# 1_interface.net
KiCad netlist of a schematic drawn in Altium Designer
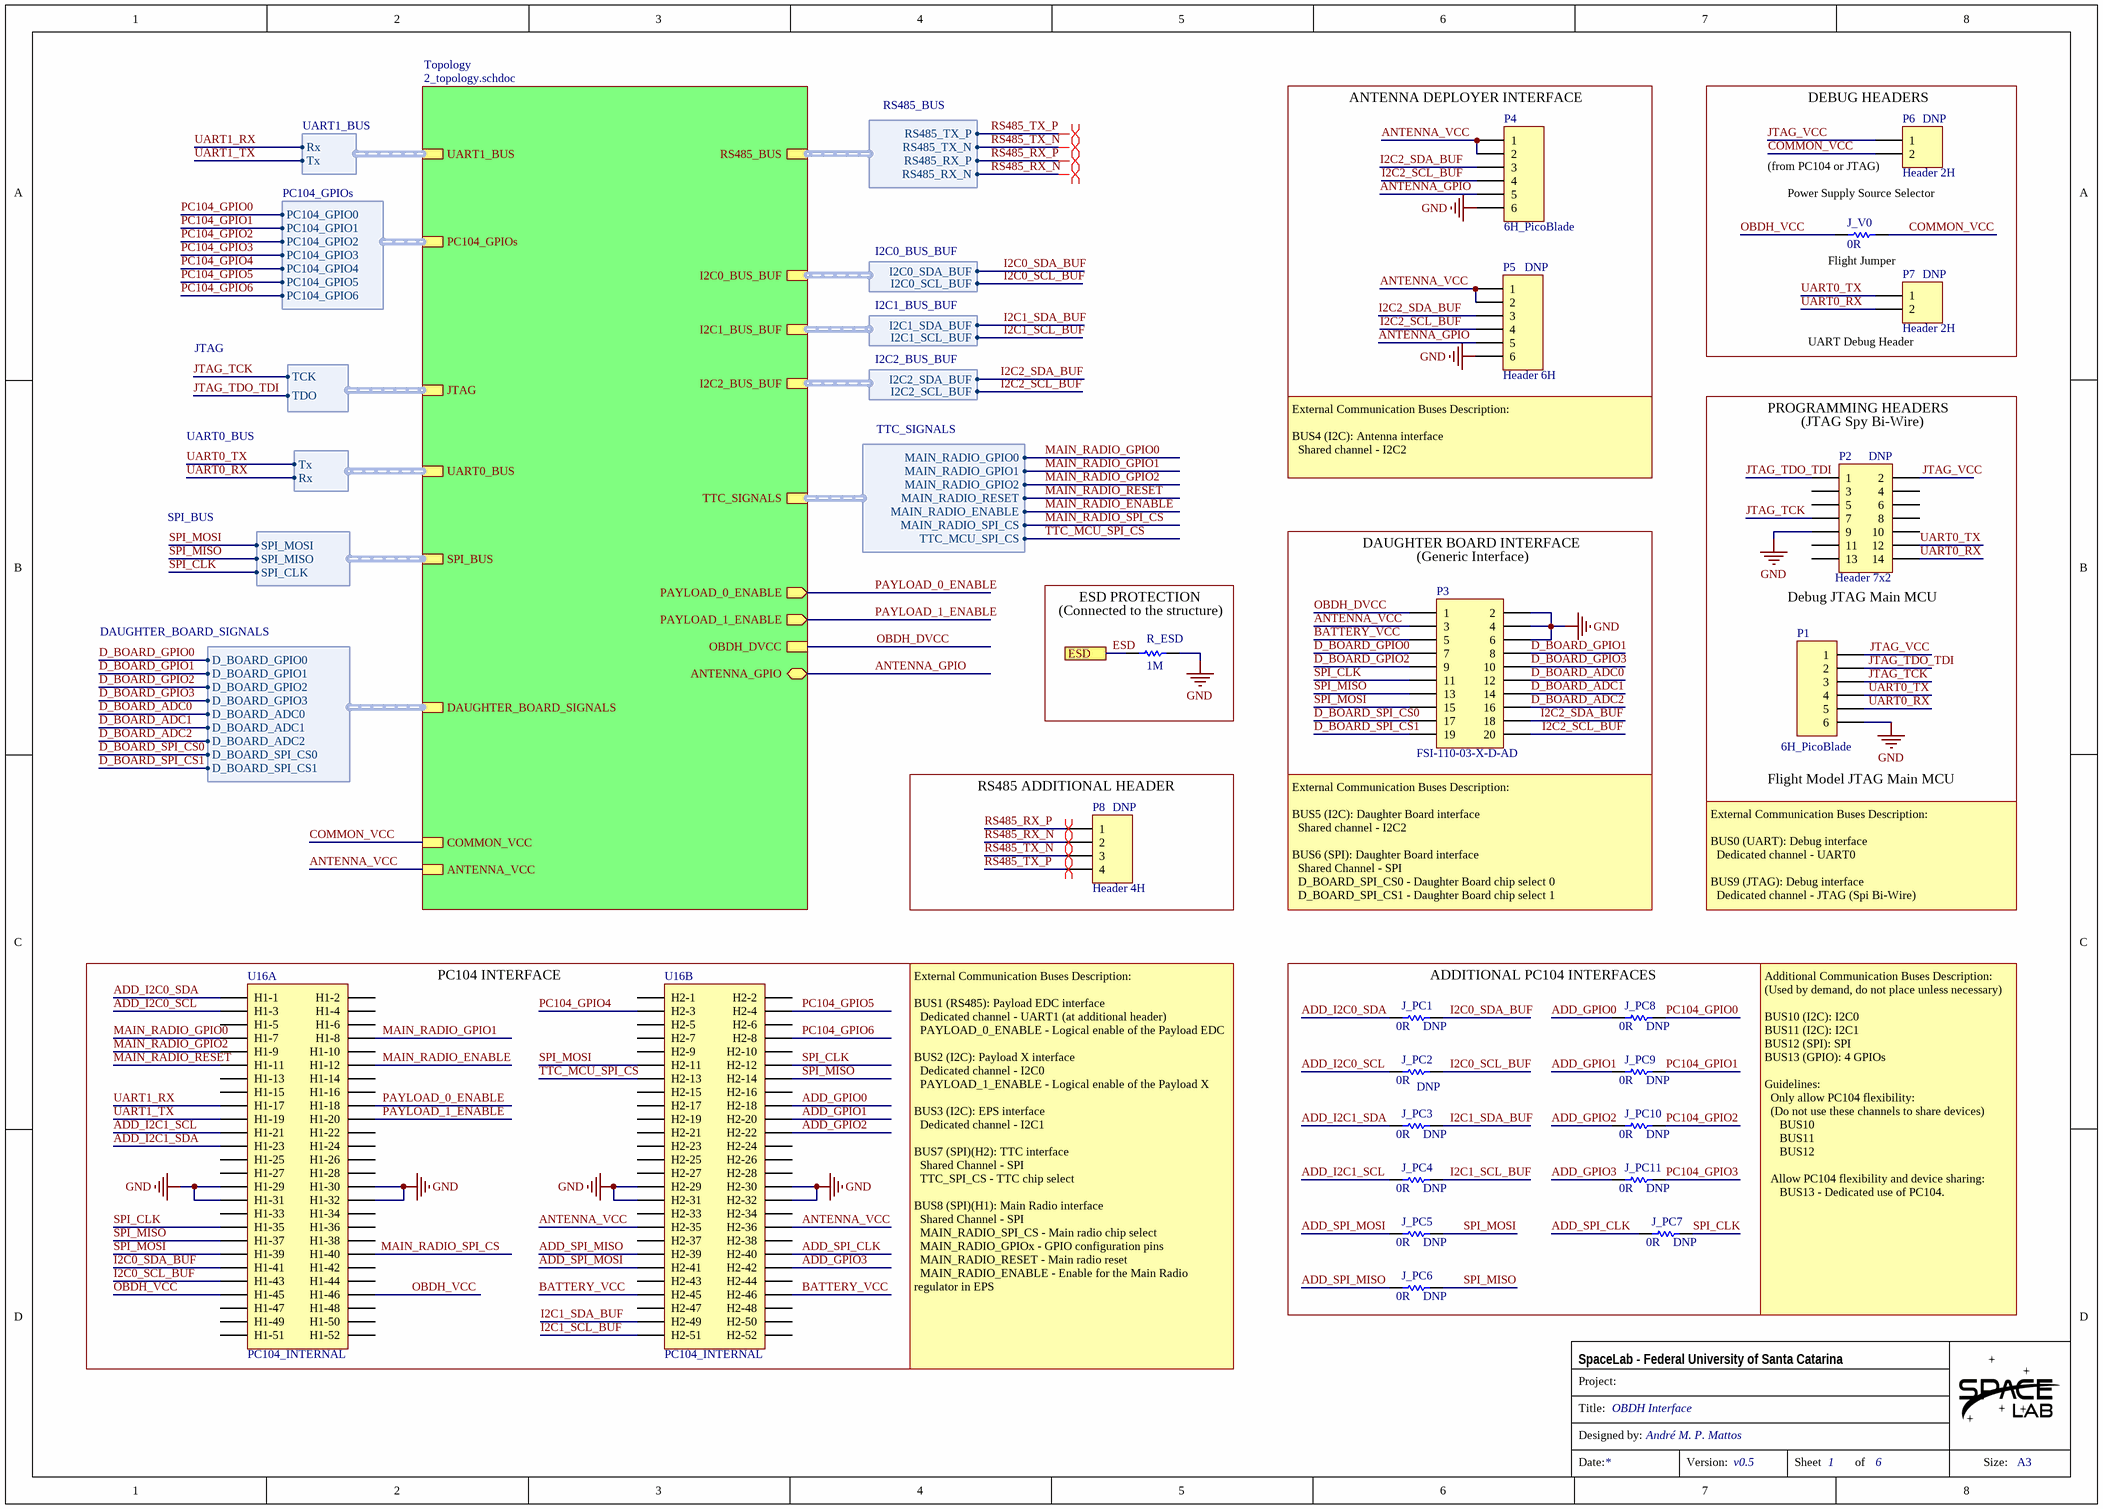
[diagram p0: 1_interface.schdoc]

(export (version "E")
  (design (tool "Eeschema 10.0.6"))
  (components
    (comp (ref "J_PC1")
      (value "0R")
      (footprint "0805")
      (description "RES 0R OHM 1/16W JUMPER 0805")
      (fields (field (name "PARTNUMBER") "CRCW08050000Z0EA"))
      (libsource (lib "OBDH_Eng_Model_2_ALT") (part "R0R_JUMPER_1/16W_0805"))
    )
    (comp (ref "J_PC2")
      (value "0R")
      (footprint "0805")
      (description "RES 0R OHM 1/16W JUMPER 0805")
      (fields (field (name "PARTNUMBER") "CRCW08050000Z0EA"))
      (libsource (lib "OBDH_Eng_Model_2_ALT") (part "R0R_JUMPER_1/16W_0805"))
    )
    (comp (ref "J_PC3")
      (value "0R")
      (footprint "0805")
      (description "RES 0R OHM 1/16W JUMPER 0805")
      (fields (field (name "PARTNUMBER") "CRCW08050000Z0EA"))
      (libsource (lib "OBDH_Eng_Model_2_ALT") (part "R0R_JUMPER_1/16W_0805"))
    )
    (comp (ref "J_PC4")
      (value "0R")
      (footprint "0805")
      (description "RES 0R OHM 1/16W JUMPER 0805")
      (fields (field (name "PARTNUMBER") "CRCW08050000Z0EA"))
      (libsource (lib "OBDH_Eng_Model_2_ALT") (part "R0R_JUMPER_1/16W_0805"))
    )
    (comp (ref "J_PC5")
      (value "0R")
      (footprint "0805")
      (description "RES 0R OHM 1/16W JUMPER 0805")
      (fields (field (name "PARTNUMBER") "CRCW08050000Z0EA"))
      (libsource (lib "OBDH_Eng_Model_2_ALT") (part "R0R_JUMPER_1/16W_0805"))
    )
    (comp (ref "J_PC6")
      (value "0R")
      (footprint "0805")
      (description "RES 0R OHM 1/16W JUMPER 0805")
      (fields (field (name "PARTNUMBER") "CRCW08050000Z0EA"))
      (libsource (lib "OBDH_Eng_Model_2_ALT") (part "R0R_JUMPER_1/16W_0805"))
    )
    (comp (ref "J_PC7")
      (value "0R")
      (footprint "0805")
      (description "RES 0R OHM 1/16W JUMPER 0805")
      (fields (field (name "PARTNUMBER") "CRCW08050000Z0EA"))
      (libsource (lib "OBDH_Eng_Model_2_ALT") (part "R0R_JUMPER_1/16W_0805"))
    )
    (comp (ref "J_PC8")
      (value "0R")
      (footprint "0805")
      (description "RES 0R OHM 1/16W JUMPER 0805")
      (fields (field (name "PARTNUMBER") "CRCW08050000Z0EA"))
      (libsource (lib "OBDH_Eng_Model_2_ALT") (part "R0R_JUMPER_1/16W_0805"))
    )
    (comp (ref "J_PC9")
      (value "0R")
      (footprint "0805")
      (description "RES 0R OHM 1/16W JUMPER 0805")
      (fields (field (name "PARTNUMBER") "CRCW08050000Z0EA"))
      (libsource (lib "OBDH_Eng_Model_2_ALT") (part "R0R_JUMPER_1/16W_0805"))
    )
    (comp (ref "J_PC10")
      (value "0R")
      (footprint "0805")
      (description "RES 0R OHM 1/16W JUMPER 0805")
      (fields (field (name "PARTNUMBER") "CRCW08050000Z0EA"))
      (libsource (lib "OBDH_Eng_Model_2_ALT") (part "R0R_JUMPER_1/16W_0805"))
    )
    (comp (ref "J_PC11")
      (value "0R")
      (footprint "0805")
      (description "RES 0R OHM 1/16W JUMPER 0805")
      (fields (field (name "PARTNUMBER") "CRCW08050000Z0EA"))
      (libsource (lib "OBDH_Eng_Model_2_ALT") (part "R0R_JUMPER_1/16W_0805"))
    )
    (comp (ref "J_V0")
      (value "0R")
      (footprint "0805")
      (description "RES 0R OHM 1/16W JUMPER 0805")
      (fields (field (name "PARTNUMBER") "CRCW08050000Z0EA"))
      (libsource (lib "OBDH_Eng_Model_2_ALT") (part "R0R_JUMPER_1/16W_0805"))
    )
    (comp (ref "P1")
      (value "6H_PicoBlade")
      (footprint "HDR6 PicoBlade")
      (description "Header, 6-Pin, Right Angle")
      (fields (field (name "PARTNUMBER") "53398-0671") (field (name "PUBLISHER") "Altium Limited"))
      (libsource (lib "") (part "Header 6H_PicoBlade_1"))
    )
    (comp (ref "P2")
      (value "Header 7x2")
      (footprint "HDR2X7")
      (description "Header, 7-Pin, Dual row")
      (fields (field (name "PUBLISHER") "Altium Limited"))
      (libsource (lib "Miscellaneous Connectors") (part "Header 7X2"))
    )
    (comp (ref "P3")
      (value "FSI-110-03-X-D-AD")
      (footprint "FSI-110-03-X-D-AD")
      (description "Contact Connector")
      (fields (field (name "PARTNUMBER") "FSI-110-03-G-D-AD"))
      (libsource (lib "OBDH_Eng_Model_2_ALT") (part "FSI-110-03-X-D-AD"))
    )
    (comp (ref "P4")
      (value "6H_PicoBlade")
      (footprint "HDR6 PicoBlade")
      (description "Header, 6-Pin, Right Angle")
      (fields (field (name "PARTNUMBER") "53398-0671") (field (name "PUBLISHER") "Altium Limited"))
      (libsource (lib "OBDH_Eng_Model_2_ALT") (part "Header 6H_PicoBlade"))
    )
    (comp (ref "P5")
      (value "Header 6H")
      (footprint "HDR1X6H")
      (description "Header, 6-Pin, Right Angle")
      (fields (field (name "PUBLISHER") "Altium Limited"))
      (libsource (lib "OBDH_Eng_Model_2_ALT") (part "Header 6H"))
    )
    (comp (ref "P6")
      (value "Header 2H")
      (footprint "HDR 1X2")
      (description "Header, 2-Pin")
      (fields (field (name "PARTNUMBER") "826646-2") (field (name "PUBLISHER") "Altium Limited"))
      (libsource (lib "OBDH_Eng_Model_2_ALT") (part "Header 2"))
    )
    (comp (ref "P7")
      (value "Header 2H")
      (footprint "HDR 1X2")
      (description "Header, 2-Pin")
      (fields (field (name "PARTNUMBER") "826646-2") (field (name "PUBLISHER") "Altium Limited"))
      (libsource (lib "OBDH_Eng_Model_2_ALT") (part "Header 2"))
    )
    (comp (ref "P8")
      (value "Header 4H")
      (footprint "HDR1X4")
      (description "Header, 4-Pin")
      (fields (field (name "PUBLISHER") "Altium Limited"))
      (libsource (lib "OBDH_Eng_Model_2_ALT") (part "Header 4H"))
    )
    (comp (ref "R_ESD")
      (value "1M")
      (footprint "0805")
      (description "RES 1000K OHM 1/8W 1% 0805")
      (fields (field (name "PARTNUMBER") "AC0805FR-13100KL"))
      (libsource (lib "OBDH_Eng_Model_2_ALT") (part "R1000k_1%_1/8W_0805"))
    )
    (comp (ref "U16")
      (value "PC104_INTERNAL")
      (footprint "PC104")
      (description "PC104")
      (fields (field (name "PARTNUMBER") "SSW-126-04-G-D"))
      (libsource (lib "OBDH_Eng_Model_2_ALT") (part "PC104"))
    )
  )
  (nets
    (net (code "13") (name "/ADD_GPIO0") (class "Default")
      (node (ref "J_PC8") (pin "1") (pinfunction "1_1") (pintype "passive"))
      (node (ref "U16") (pin "H2-18") (pinfunction "H2-18_H2-18") (pintype "passive"))
    )
    (net (code "14") (name "/ADD_GPIO1") (class "Default")
      (node (ref "J_PC9") (pin "1") (pinfunction "1_1") (pintype "passive"))
      (node (ref "U16") (pin "H2-20") (pinfunction "H2-20_H2-20") (pintype "passive"))
    )
    (net (code "15") (name "/ADD_GPIO2") (class "Default")
      (node (ref "J_PC10") (pin "1") (pinfunction "1_1") (pintype "passive"))
      (node (ref "U16") (pin "H2-22") (pinfunction "H2-22_H2-22") (pintype "passive"))
    )
    (net (code "16") (name "/ADD_GPIO3") (class "Default")
      (node (ref "J_PC11") (pin "1") (pinfunction "1_1") (pintype "passive"))
      (node (ref "U16") (pin "H2-42") (pinfunction "H2-42_H2-42") (pintype "passive"))
    )
    (net (code "17") (name "/ADD_I2C0_SCL") (class "Default")
      (node (ref "J_PC2") (pin "1") (pinfunction "1_1") (pintype "passive"))
      (node (ref "U16") (pin "H1-3") (pinfunction "H1-3_H1-3") (pintype "passive"))
    )
    (net (code "18") (name "/ADD_I2C0_SDA") (class "Default")
      (node (ref "J_PC1") (pin "1") (pinfunction "1_1") (pintype "passive"))
      (node (ref "U16") (pin "H1-1") (pinfunction "H1-1_H1-1") (pintype "passive"))
    )
    (net (code "19") (name "/ADD_I2C1_SCL") (class "Default")
      (node (ref "J_PC4") (pin "1") (pinfunction "1_1") (pintype "passive"))
      (node (ref "U16") (pin "H1-21") (pinfunction "H1-21_H1-21") (pintype "passive"))
    )
    (net (code "20") (name "/ADD_I2C1_SDA") (class "Default")
      (node (ref "J_PC3") (pin "1") (pinfunction "1_1") (pintype "passive"))
      (node (ref "U16") (pin "H1-23") (pinfunction "H1-23_H1-23") (pintype "passive"))
    )
    (net (code "21") (name "/ADD_SPI_CLK") (class "Default")
      (node (ref "J_PC7") (pin "1") (pinfunction "1_1") (pintype "passive"))
      (node (ref "U16") (pin "H2-40") (pinfunction "H2-40_H2-40") (pintype "passive"))
    )
    (net (code "22") (name "/ADD_SPI_MISO") (class "Default")
      (node (ref "J_PC6") (pin "1") (pinfunction "1_1") (pintype "passive"))
      (node (ref "U16") (pin "H2-39") (pinfunction "H2-39_H2-39") (pintype "passive"))
    )
    (net (code "23") (name "/ADD_SPI_MOSI") (class "Default")
      (node (ref "J_PC5") (pin "1") (pinfunction "1_1") (pintype "passive"))
      (node (ref "U16") (pin "H2-41") (pinfunction "H2-41_H2-41") (pintype "passive"))
    )
    (net (code "24") (name "/ANTENNA_GPIO") (class "Default")
      (node (ref "P4") (pin "5") (pinfunction "5_5") (pintype "passive"))
      (node (ref "P5") (pin "5") (pinfunction "5_5") (pintype "passive"))
    )
    (net (code "25") (name "/ANTENNA_VCC") (class "Default")
      (node (ref "P3") (pin "3") (pinfunction "3_3") (pintype "passive"))
      (node (ref "P4") (pin "1") (pinfunction "1_1") (pintype "passive"))
      (node (ref "P4") (pin "2") (pinfunction "2_2") (pintype "passive"))
      (node (ref "P5") (pin "1") (pinfunction "1_1") (pintype "passive"))
      (node (ref "P5") (pin "2") (pinfunction "2_2") (pintype "passive"))
      (node (ref "U16") (pin "H2-35") (pinfunction "H2-35_H2-35") (pintype "passive"))
      (node (ref "U16") (pin "H2-36") (pinfunction "H2-36_H2-36") (pintype "passive"))
    )
    (net (code "26") (name "/BATTERY_VCC") (class "Default")
      (node (ref "P3") (pin "5") (pinfunction "5_5") (pintype "passive"))
      (node (ref "U16") (pin "H2-45") (pinfunction "H2-45_H2-45") (pintype "passive"))
      (node (ref "U16") (pin "H2-46") (pinfunction "H2-46_H2-46") (pintype "passive"))
    )
    (net (code "27") (name "/COMMON_VCC") (class "Default")
      (node (ref "J_V0") (pin "2") (pinfunction "2_2") (pintype "passive"))
      (node (ref "P6") (pin "2") (pinfunction "2_2") (pintype "passive"))
    )
    (net (code "28") (name "/D_BOARD_ADC0") (class "Default")
      (node (ref "P3") (pin "12") (pinfunction "12_12") (pintype "passive"))
    )
    (net (code "29") (name "/D_BOARD_ADC1") (class "Default")
      (node (ref "P3") (pin "14") (pinfunction "14_14") (pintype "passive"))
    )
    (net (code "30") (name "/D_BOARD_ADC2") (class "Default")
      (node (ref "P3") (pin "16") (pinfunction "16_16") (pintype "passive"))
    )
    (net (code "31") (name "/D_BOARD_GPIO0") (class "Default")
      (node (ref "P3") (pin "7") (pinfunction "7_7") (pintype "passive"))
    )
    (net (code "32") (name "/D_BOARD_GPIO1") (class "Default")
      (node (ref "P3") (pin "8") (pinfunction "8_8") (pintype "passive"))
    )
    (net (code "33") (name "/D_BOARD_GPIO2") (class "Default")
      (node (ref "P3") (pin "9") (pinfunction "9_9") (pintype "passive"))
    )
    (net (code "34") (name "/D_BOARD_GPIO3") (class "Default")
      (node (ref "P3") (pin "10") (pinfunction "10_10") (pintype "passive"))
    )
    (net (code "35") (name "/D_BOARD_SPI_CS0") (class "Default")
      (node (ref "P3") (pin "17") (pinfunction "17_17") (pintype "passive"))
    )
    (net (code "36") (name "/D_BOARD_SPI_CS1") (class "Default")
      (node (ref "P3") (pin "19") (pinfunction "19_19") (pintype "passive"))
    )
    (net (code "37") (name "/ESD") (class "Default")
      (node (ref "R_ESD") (pin "2") (pinfunction "2_2") (pintype "passive"))
    )
    (net (code "38") (name "/I2C0_SCL_BUF") (class "Default")
      (node (ref "J_PC2") (pin "2") (pinfunction "2_2") (pintype "passive"))
      (node (ref "U16") (pin "H1-43") (pinfunction "H1-43_H1-43") (pintype "passive"))
    )
    (net (code "39") (name "/I2C0_SDA_BUF") (class "Default")
      (node (ref "J_PC1") (pin "2") (pinfunction "2_2") (pintype "passive"))
      (node (ref "U16") (pin "H1-41") (pinfunction "H1-41_H1-41") (pintype "passive"))
    )
    (net (code "40") (name "/I2C1_SCL_BUF") (class "Default")
      (node (ref "J_PC4") (pin "2") (pinfunction "2_2") (pintype "passive"))
      (node (ref "U16") (pin "H2-51") (pinfunction "H2-51_H2-51") (pintype "passive"))
    )
    (net (code "41") (name "/I2C1_SDA_BUF") (class "Default")
      (node (ref "J_PC3") (pin "2") (pinfunction "2_2") (pintype "passive"))
      (node (ref "U16") (pin "H2-49") (pinfunction "H2-49_H2-49") (pintype "passive"))
    )
    (net (code "42") (name "/I2C2_SCL_BUF") (class "Default")
      (node (ref "P3") (pin "20") (pinfunction "20_20") (pintype "passive"))
      (node (ref "P4") (pin "4") (pinfunction "4_4") (pintype "passive"))
      (node (ref "P5") (pin "4") (pinfunction "4_4") (pintype "passive"))
    )
    (net (code "43") (name "/I2C2_SDA_BUF") (class "Default")
      (node (ref "P3") (pin "18") (pinfunction "18_18") (pintype "passive"))
      (node (ref "P4") (pin "3") (pinfunction "3_3") (pintype "passive"))
      (node (ref "P5") (pin "3") (pinfunction "3_3") (pintype "passive"))
    )
    (net (code "44") (name "/JTAG_TCK") (class "Default")
      (node (ref "P1") (pin "3") (pinfunction "3_3") (pintype "passive"))
      (node (ref "P2") (pin "7") (pinfunction "7_7") (pintype "passive"))
    )
    (net (code "45") (name "/JTAG_TDO_TDI") (class "Default")
      (node (ref "P1") (pin "2") (pinfunction "2_2") (pintype "passive"))
      (node (ref "P2") (pin "1") (pinfunction "1_1") (pintype "passive"))
    )
    (net (code "46") (name "/JTAG_VCC") (class "Default")
      (node (ref "P1") (pin "1") (pinfunction "1_1") (pintype "passive"))
      (node (ref "P2") (pin "2") (pinfunction "2_2") (pintype "passive"))
      (node (ref "P6") (pin "1") (pinfunction "1_1") (pintype "passive"))
    )
    (net (code "47") (name "/MAIN_RADIO_ENABLE") (class "Default")
      (node (ref "U16") (pin "H1-12") (pinfunction "H1-12_H1-12") (pintype "passive"))
    )
    (net (code "48") (name "/MAIN_RADIO_GPIO0") (class "Default")
      (node (ref "U16") (pin "H1-7") (pinfunction "H1-7_H1-7") (pintype "passive"))
    )
    (net (code "49") (name "/MAIN_RADIO_GPIO1") (class "Default")
      (node (ref "U16") (pin "H1-8") (pinfunction "H1-8_H1-8") (pintype "passive"))
    )
    (net (code "50") (name "/MAIN_RADIO_GPIO2") (class "Default")
      (node (ref "U16") (pin "H1-9") (pinfunction "H1-9_H1-9") (pintype "passive"))
    )
    (net (code "51") (name "/MAIN_RADIO_RESET") (class "Default")
      (node (ref "U16") (pin "H1-11") (pinfunction "H1-11_H1-11") (pintype "passive"))
    )
    (net (code "52") (name "/MAIN_RADIO_SPI_CS") (class "Default")
      (node (ref "U16") (pin "H1-40") (pinfunction "H1-40_H1-40") (pintype "passive"))
    )
    (net (code "53") (name "/OBDH_DVCC") (class "Default")
      (node (ref "P3") (pin "1") (pinfunction "1_1") (pintype "passive"))
    )
    (net (code "54") (name "/OBDH_VCC") (class "Default")
      (node (ref "J_V0") (pin "1") (pinfunction "1_1") (pintype "passive"))
      (node (ref "U16") (pin "H1-45") (pinfunction "H1-45_H1-45") (pintype "passive"))
      (node (ref "U16") (pin "H1-46") (pinfunction "H1-46_H1-46") (pintype "passive"))
    )
    (net (code "55") (name "/PAYLOAD_0_ENABLE") (class "Default")
      (node (ref "U16") (pin "H1-18") (pinfunction "H1-18_H1-18") (pintype "passive"))
    )
    (net (code "56") (name "/PAYLOAD_1_ENABLE") (class "Default")
      (node (ref "U16") (pin "H1-20") (pinfunction "H1-20_H1-20") (pintype "passive"))
    )
    (net (code "57") (name "/PC104_GPIO0") (class "Default")
      (node (ref "J_PC8") (pin "2") (pinfunction "2_2") (pintype "passive"))
    )
    (net (code "58") (name "/PC104_GPIO1") (class "Default")
      (node (ref "J_PC9") (pin "2") (pinfunction "2_2") (pintype "passive"))
    )
    (net (code "59") (name "/PC104_GPIO2") (class "Default")
      (node (ref "J_PC10") (pin "2") (pinfunction "2_2") (pintype "passive"))
    )
    (net (code "60") (name "/PC104_GPIO3") (class "Default")
      (node (ref "J_PC11") (pin "2") (pinfunction "2_2") (pintype "passive"))
    )
    (net (code "61") (name "/PC104_GPIO4") (class "Default")
      (node (ref "U16") (pin "H2-3") (pinfunction "H2-3_H2-3") (pintype "passive"))
    )
    (net (code "62") (name "/PC104_GPIO5") (class "Default")
      (node (ref "U16") (pin "H2-4") (pinfunction "H2-4_H2-4") (pintype "passive"))
    )
    (net (code "63") (name "/PC104_GPIO6") (class "Default")
      (node (ref "U16") (pin "H2-8") (pinfunction "H2-8_H2-8") (pintype "passive"))
    )
    (net (code "64") (name "/RS485_RX_N") (class "Default")
      (node (ref "P8") (pin "2") (pinfunction "2_2") (pintype "passive"))
    )
    (net (code "65") (name "/RS485_RX_P") (class "Default")
      (node (ref "P8") (pin "1") (pinfunction "1_1") (pintype "passive"))
    )
    (net (code "66") (name "/RS485_TX_N") (class "Default")
      (node (ref "P8") (pin "3") (pinfunction "3_3") (pintype "passive"))
    )
    (net (code "67") (name "/RS485_TX_P") (class "Default")
      (node (ref "P8") (pin "4") (pinfunction "4_4") (pintype "passive"))
    )
    (net (code "68") (name "/SPI_CLK") (class "Default")
      (node (ref "J_PC7") (pin "2") (pinfunction "2_2") (pintype "passive"))
      (node (ref "P3") (pin "11") (pinfunction "11_11") (pintype "passive"))
      (node (ref "U16") (pin "H1-35") (pinfunction "H1-35_H1-35") (pintype "passive"))
      (node (ref "U16") (pin "H2-12") (pinfunction "H2-12_H2-12") (pintype "passive"))
    )
    (net (code "69") (name "/SPI_MISO") (class "Default")
      (node (ref "J_PC6") (pin "2") (pinfunction "2_2") (pintype "passive"))
      (node (ref "P3") (pin "13") (pinfunction "13_13") (pintype "passive"))
      (node (ref "U16") (pin "H1-37") (pinfunction "H1-37_H1-37") (pintype "passive"))
      (node (ref "U16") (pin "H2-14") (pinfunction "H2-14_H2-14") (pintype "passive"))
    )
    (net (code "70") (name "/SPI_MOSI") (class "Default")
      (node (ref "J_PC5") (pin "2") (pinfunction "2_2") (pintype "passive"))
      (node (ref "P3") (pin "15") (pinfunction "15_15") (pintype "passive"))
      (node (ref "U16") (pin "H1-39") (pinfunction "H1-39_H1-39") (pintype "passive"))
      (node (ref "U16") (pin "H2-11") (pinfunction "H2-11_H2-11") (pintype "passive"))
    )
    (net (code "71") (name "/TTC_MCU_SPI_CS") (class "Default")
      (node (ref "U16") (pin "H2-13") (pinfunction "H2-13_H2-13") (pintype "passive"))
    )
    (net (code "72") (name "/UART0_RX") (class "Default")
      (node (ref "P1") (pin "5") (pinfunction "5_5") (pintype "passive"))
      (node (ref "P2") (pin "14") (pinfunction "14_14") (pintype "passive"))
      (node (ref "P7") (pin "2") (pinfunction "2_2") (pintype "passive"))
    )
    (net (code "73") (name "/UART0_TX") (class "Default")
      (node (ref "P1") (pin "4") (pinfunction "4_4") (pintype "passive"))
      (node (ref "P2") (pin "12") (pinfunction "12_12") (pintype "passive"))
      (node (ref "P7") (pin "1") (pinfunction "1_1") (pintype "passive"))
    )
    (net (code "74") (name "/UART1_RX") (class "Default")
      (node (ref "U16") (pin "H1-17") (pinfunction "H1-17_H1-17") (pintype "passive"))
    )
    (net (code "75") (name "/UART1_TX") (class "Default")
      (node (ref "U16") (pin "H1-19") (pinfunction "H1-19_H1-19") (pintype "passive"))
    )
    (net (code "87") (name "GND") (class "Default")
      (node (ref "P1") (pin "6") (pinfunction "6_6") (pintype "passive"))
      (node (ref "P2") (pin "9") (pinfunction "9_9") (pintype "passive"))
      (node (ref "P3") (pin "2") (pinfunction "2_2") (pintype "passive"))
      (node (ref "P3") (pin "4") (pinfunction "4_4") (pintype "passive"))
      (node (ref "P3") (pin "6") (pinfunction "6_6") (pintype "passive"))
      (node (ref "P4") (pin "6") (pinfunction "6_6") (pintype "passive"))
      (node (ref "P5") (pin "6") (pinfunction "6_6") (pintype "passive"))
      (node (ref "R_ESD") (pin "1") (pinfunction "1_1") (pintype "passive"))
      (node (ref "U16") (pin "H1-29") (pinfunction "H1-29_H1-29") (pintype "passive"))
      (node (ref "U16") (pin "H1-30") (pinfunction "H1-30_H1-30") (pintype "passive"))
      (node (ref "U16") (pin "H1-31") (pinfunction "H1-31_H1-31") (pintype "passive"))
      (node (ref "U16") (pin "H1-32") (pinfunction "H1-32_H1-32") (pintype "passive"))
      (node (ref "U16") (pin "H2-29") (pinfunction "H2-29_H2-29") (pintype "passive"))
      (node (ref "U16") (pin "H2-30") (pinfunction "H2-30_H2-30") (pintype "passive"))
      (node (ref "U16") (pin "H2-31") (pinfunction "H2-31_H2-31") (pintype "passive"))
      (node (ref "U16") (pin "H2-32") (pinfunction "H2-32_H2-32") (pintype "passive"))
    )
    (net (code "88") (name "unconnected-(P2-Pad3)") (class "Default")
      (node (ref "P2") (pin "3") (pinfunction "3_3") (pintype "passive"))
    )
    (net (code "89") (name "unconnected-(P2-Pad4)") (class "Default")
      (node (ref "P2") (pin "4") (pinfunction "4_4") (pintype "passive"))
    )
    (net (code "90") (name "unconnected-(P2-Pad5)") (class "Default")
      (node (ref "P2") (pin "5") (pinfunction "5_5") (pintype "passive"))
    )
    (net (code "91") (name "unconnected-(P2-Pad6)") (class "Default")
      (node (ref "P2") (pin "6") (pinfunction "6_6") (pintype "passive"))
    )
    (net (code "92") (name "unconnected-(P2-Pad8)") (class "Default")
      (node (ref "P2") (pin "8") (pinfunction "8_8") (pintype "passive"))
    )
    (net (code "93") (name "unconnected-(P2-Pad10)") (class "Default")
      (node (ref "P2") (pin "10") (pinfunction "10_10") (pintype "passive"))
    )
    (net (code "94") (name "unconnected-(P2-Pad11)") (class "Default")
      (node (ref "P2") (pin "11") (pinfunction "11_11") (pintype "passive"))
    )
    (net (code "95") (name "unconnected-(P2-Pad13)") (class "Default")
      (node (ref "P2") (pin "13") (pinfunction "13_13") (pintype "passive"))
    )
    (net (code "96") (name "unconnected-(U16-PadH1-2)") (class "Default")
      (node (ref "U16") (pin "H1-2") (pinfunction "H1-2_H1-2") (pintype "passive"))
    )
    (net (code "97") (name "unconnected-(U16-PadH1-4)") (class "Default")
      (node (ref "U16") (pin "H1-4") (pinfunction "H1-4_H1-4") (pintype "passive"))
    )
    (net (code "98") (name "unconnected-(U16-PadH1-5)") (class "Default")
      (node (ref "U16") (pin "H1-5") (pinfunction "H1-5_H1-5") (pintype "passive"))
    )
    (net (code "99") (name "unconnected-(U16-PadH1-6)") (class "Default")
      (node (ref "U16") (pin "H1-6") (pinfunction "H1-6_H1-6") (pintype "passive"))
    )
    (net (code "100") (name "unconnected-(U16-PadH1-10)") (class "Default")
      (node (ref "U16") (pin "H1-10") (pinfunction "H1-10_H1-10") (pintype "passive"))
    )
    (net (code "101") (name "unconnected-(U16-PadH1-13)") (class "Default")
      (node (ref "U16") (pin "H1-13") (pinfunction "H1-13_H1-13") (pintype "passive"))
    )
    (net (code "102") (name "unconnected-(U16-PadH1-14)") (class "Default")
      (node (ref "U16") (pin "H1-14") (pinfunction "H1-14_H1-14") (pintype "passive"))
    )
    (net (code "103") (name "unconnected-(U16-PadH1-15)") (class "Default")
      (node (ref "U16") (pin "H1-15") (pinfunction "H1-15_H1-15") (pintype "passive"))
    )
    (net (code "104") (name "unconnected-(U16-PadH1-16)") (class "Default")
      (node (ref "U16") (pin "H1-16") (pinfunction "H1-16_H1-16") (pintype "passive"))
    )
    (net (code "105") (name "unconnected-(U16-PadH1-22)") (class "Default")
      (node (ref "U16") (pin "H1-22") (pinfunction "H1-22_H1-22") (pintype "passive"))
    )
    (net (code "106") (name "unconnected-(U16-PadH1-24)") (class "Default")
      (node (ref "U16") (pin "H1-24") (pinfunction "H1-24_H1-24") (pintype "passive"))
    )
    (net (code "107") (name "unconnected-(U16-PadH1-25)") (class "Default")
      (node (ref "U16") (pin "H1-25") (pinfunction "H1-25_H1-25") (pintype "passive"))
    )
    (net (code "108") (name "unconnected-(U16-PadH1-26)") (class "Default")
      (node (ref "U16") (pin "H1-26") (pinfunction "H1-26_H1-26") (pintype "passive"))
    )
    (net (code "109") (name "unconnected-(U16-PadH1-27)") (class "Default")
      (node (ref "U16") (pin "H1-27") (pinfunction "H1-27_H1-27") (pintype "passive"))
    )
    (net (code "110") (name "unconnected-(U16-PadH1-28)") (class "Default")
      (node (ref "U16") (pin "H1-28") (pinfunction "H1-28_H1-28") (pintype "passive"))
    )
    (net (code "111") (name "unconnected-(U16-PadH1-33)") (class "Default")
      (node (ref "U16") (pin "H1-33") (pinfunction "H1-33_H1-33") (pintype "passive"))
    )
    (net (code "112") (name "unconnected-(U16-PadH1-34)") (class "Default")
      (node (ref "U16") (pin "H1-34") (pinfunction "H1-34_H1-34") (pintype "passive"))
    )
    (net (code "113") (name "unconnected-(U16-PadH1-36)") (class "Default")
      (node (ref "U16") (pin "H1-36") (pinfunction "H1-36_H1-36") (pintype "passive"))
    )
    (net (code "114") (name "unconnected-(U16-PadH1-38)") (class "Default")
      (node (ref "U16") (pin "H1-38") (pinfunction "H1-38_H1-38") (pintype "passive"))
    )
    (net (code "115") (name "unconnected-(U16-PadH1-42)") (class "Default")
      (node (ref "U16") (pin "H1-42") (pinfunction "H1-42_H1-42") (pintype "passive"))
    )
    (net (code "116") (name "unconnected-(U16-PadH1-44)") (class "Default")
      (node (ref "U16") (pin "H1-44") (pinfunction "H1-44_H1-44") (pintype "passive"))
    )
    (net (code "117") (name "unconnected-(U16-PadH1-47)") (class "Default")
      (node (ref "U16") (pin "H1-47") (pinfunction "H1-47_H1-47") (pintype "passive"))
    )
    (net (code "118") (name "unconnected-(U16-PadH1-48)") (class "Default")
      (node (ref "U16") (pin "H1-48") (pinfunction "H1-48_H1-48") (pintype "passive"))
    )
    (net (code "119") (name "unconnected-(U16-PadH1-49)") (class "Default")
      (node (ref "U16") (pin "H1-49") (pinfunction "H1-49_H1-49") (pintype "passive"))
    )
    (net (code "120") (name "unconnected-(U16-PadH1-50)") (class "Default")
      (node (ref "U16") (pin "H1-50") (pinfunction "H1-50_H1-50") (pintype "passive"))
    )
    (net (code "121") (name "unconnected-(U16-PadH1-51)") (class "Default")
      (node (ref "U16") (pin "H1-51") (pinfunction "H1-51_H1-51") (pintype "passive"))
    )
    (net (code "122") (name "unconnected-(U16-PadH1-52)") (class "Default")
      (node (ref "U16") (pin "H1-52") (pinfunction "H1-52_H1-52") (pintype "passive"))
    )
    (net (code "123") (name "unconnected-(U16-PadH2-1)") (class "Default")
      (node (ref "U16") (pin "H2-1") (pinfunction "H2-1_H2-1") (pintype "passive"))
    )
    (net (code "124") (name "unconnected-(U16-PadH2-2)") (class "Default")
      (node (ref "U16") (pin "H2-2") (pinfunction "H2-2_H2-2") (pintype "passive"))
    )
    (net (code "125") (name "unconnected-(U16-PadH2-5)") (class "Default")
      (node (ref "U16") (pin "H2-5") (pinfunction "H2-5_H2-5") (pintype "passive"))
    )
    (net (code "126") (name "unconnected-(U16-PadH2-6)") (class "Default")
      (node (ref "U16") (pin "H2-6") (pinfunction "H2-6_H2-6") (pintype "passive"))
    )
    (net (code "127") (name "unconnected-(U16-PadH2-7)") (class "Default")
      (node (ref "U16") (pin "H2-7") (pinfunction "H2-7_H2-7") (pintype "passive"))
    )
    (net (code "128") (name "unconnected-(U16-PadH2-9)") (class "Default")
      (node (ref "U16") (pin "H2-9") (pinfunction "H2-9_H2-9") (pintype "passive"))
    )
    (net (code "129") (name "unconnected-(U16-PadH2-10)") (class "Default")
      (node (ref "U16") (pin "H2-10") (pinfunction "H2-10_H2-10") (pintype "passive"))
    )
    (net (code "130") (name "unconnected-(U16-PadH2-15)") (class "Default")
      (node (ref "U16") (pin "H2-15") (pinfunction "H2-15_H2-15") (pintype "passive"))
    )
    (net (code "131") (name "unconnected-(U16-PadH2-16)") (class "Default")
      (node (ref "U16") (pin "H2-16") (pinfunction "H2-16_H2-16") (pintype "passive"))
    )
    (net (code "132") (name "unconnected-(U16-PadH2-17)") (class "Default")
      (node (ref "U16") (pin "H2-17") (pinfunction "H2-17_H2-17") (pintype "passive"))
    )
    (net (code "133") (name "unconnected-(U16-PadH2-19)") (class "Default")
      (node (ref "U16") (pin "H2-19") (pinfunction "H2-19_H2-19") (pintype "passive"))
    )
    (net (code "134") (name "unconnected-(U16-PadH2-21)") (class "Default")
      (node (ref "U16") (pin "H2-21") (pinfunction "H2-21_H2-21") (pintype "passive"))
    )
    (net (code "135") (name "unconnected-(U16-PadH2-23)") (class "Default")
      (node (ref "U16") (pin "H2-23") (pinfunction "H2-23_H2-23") (pintype "passive"))
    )
    (net (code "136") (name "unconnected-(U16-PadH2-24)") (class "Default")
      (node (ref "U16") (pin "H2-24") (pinfunction "H2-24_H2-24") (pintype "passive"))
    )
    (net (code "137") (name "unconnected-(U16-PadH2-25)") (class "Default")
      (node (ref "U16") (pin "H2-25") (pinfunction "H2-25_H2-25") (pintype "passive"))
    )
    (net (code "138") (name "unconnected-(U16-PadH2-26)") (class "Default")
      (node (ref "U16") (pin "H2-26") (pinfunction "H2-26_H2-26") (pintype "passive"))
    )
    (net (code "139") (name "unconnected-(U16-PadH2-27)") (class "Default")
      (node (ref "U16") (pin "H2-27") (pinfunction "H2-27_H2-27") (pintype "passive"))
    )
    (net (code "140") (name "unconnected-(U16-PadH2-28)") (class "Default")
      (node (ref "U16") (pin "H2-28") (pinfunction "H2-28_H2-28") (pintype "passive"))
    )
    (net (code "141") (name "unconnected-(U16-PadH2-33)") (class "Default")
      (node (ref "U16") (pin "H2-33") (pinfunction "H2-33_H2-33") (pintype "passive"))
    )
    (net (code "142") (name "unconnected-(U16-PadH2-34)") (class "Default")
      (node (ref "U16") (pin "H2-34") (pinfunction "H2-34_H2-34") (pintype "passive"))
    )
    (net (code "143") (name "unconnected-(U16-PadH2-37)") (class "Default")
      (node (ref "U16") (pin "H2-37") (pinfunction "H2-37_H2-37") (pintype "passive"))
    )
    (net (code "144") (name "unconnected-(U16-PadH2-38)") (class "Default")
      (node (ref "U16") (pin "H2-38") (pinfunction "H2-38_H2-38") (pintype "passive"))
    )
    (net (code "145") (name "unconnected-(U16-PadH2-43)") (class "Default")
      (node (ref "U16") (pin "H2-43") (pinfunction "H2-43_H2-43") (pintype "passive"))
    )
    (net (code "146") (name "unconnected-(U16-PadH2-44)") (class "Default")
      (node (ref "U16") (pin "H2-44") (pinfunction "H2-44_H2-44") (pintype "passive"))
    )
    (net (code "147") (name "unconnected-(U16-PadH2-47)") (class "Default")
      (node (ref "U16") (pin "H2-47") (pinfunction "H2-47_H2-47") (pintype "passive"))
    )
    (net (code "148") (name "unconnected-(U16-PadH2-48)") (class "Default")
      (node (ref "U16") (pin "H2-48") (pinfunction "H2-48_H2-48") (pintype "passive"))
    )
    (net (code "149") (name "unconnected-(U16-PadH2-50)") (class "Default")
      (node (ref "U16") (pin "H2-50") (pinfunction "H2-50_H2-50") (pintype "passive"))
    )
    (net (code "150") (name "unconnected-(U16-PadH2-52)") (class "Default")
      (node (ref "U16") (pin "H2-52") (pinfunction "H2-52_H2-52") (pintype "passive"))
    )
  )
)
